# Page_H_B2B_A.net
KiCad netlist of a schematic drawn in Altium Designer
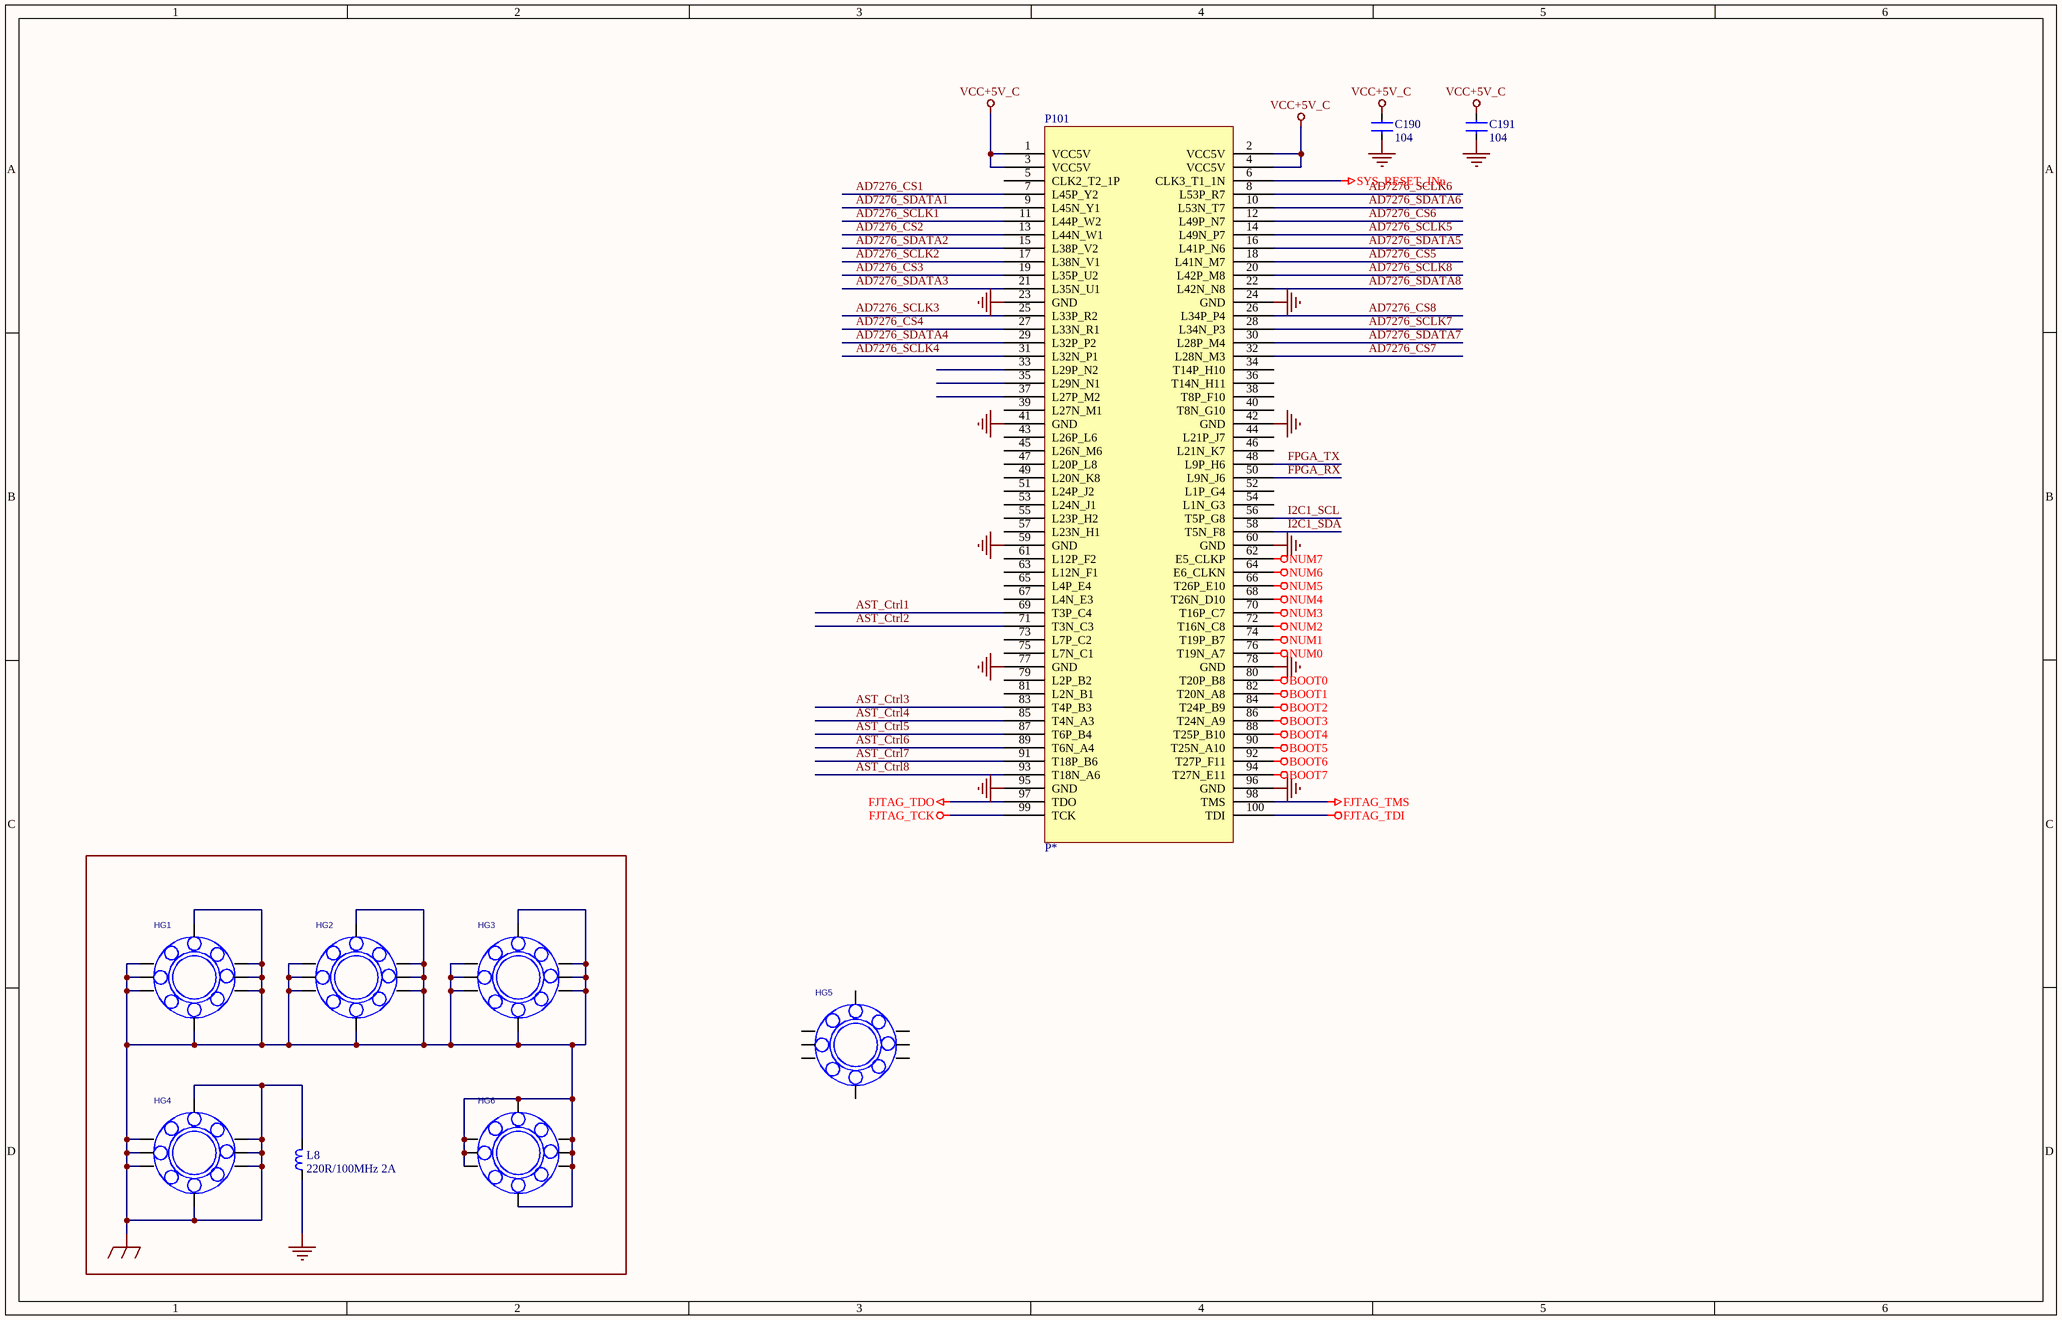
[diagram p0: Page H_B2B_A.SchDoc]

(export (version "E")
  (design (tool "Eeschema 10.0.6"))
  (components
    (comp (ref "C190")
      (value "104")
      (footprint "0603C")
      (description "C-X5R/X7R")
      (libsource (lib "贴片电阻电容") (part "C-X5R/X7R"))
    )
    (comp (ref "C191")
      (value "104")
      (footprint "0603C")
      (description "C-X5R/X7R")
      (libsource (lib "贴片电阻电容") (part "C-X5R/X7R"))
    )
    (comp (ref "HG1")
      (value "MOUNTING_HOLE_NL")
      (footprint "th126_196c_13c")
      (description "Sym, PCB mounting holes, th126_196c_13c")
      (libsource (lib "*") (part "MOUNTING_HOLE"))
    )
    (comp (ref "HG2")
      (value "MOUNTING_HOLE_NL")
      (footprint "th126_196c_13c")
      (description "Sym, PCB mounting holes, th126_196c_13c")
      (libsource (lib "*") (part "MOUNTING_HOLE"))
    )
    (comp (ref "HG3")
      (value "MOUNTING_HOLE_NL")
      (footprint "th126_196c_13c")
      (description "Sym, PCB mounting holes, th126_196c_13c")
      (libsource (lib "*") (part "MOUNTING_HOLE"))
    )
    (comp (ref "HG4")
      (value "MOUNTING_HOLE_NL")
      (footprint "th126_196c_13c")
      (description "Sym, PCB mounting holes, th126_196c_13c")
      (libsource (lib "*") (part "MOUNTING_HOLE"))
    )
    (comp (ref "HG5")
      (value "MOUNTING_HOLE_NL")
      (footprint "th126_196c_13c")
      (description "Sym, PCB mounting holes, th126_196c_13c")
      (libsource (lib "*") (part "MOUNTING_HOLE"))
    )
    (comp (ref "HG6")
      (value "MOUNTING_HOLE_NL")
      (footprint "th126_196c_13c")
      (description "Sym, PCB mounting holes, th126_196c_13c")
      (libsource (lib "*") (part "MOUNTING_HOLE"))
    )
    (comp (ref "L8")
      (value "220R/100MHz 2A")
      (footprint "0603R")
      (libsource (lib "电感、变压器件") (part "Inductor"))
    )
    (comp (ref "P101") (value "P*") (footprint "IDC100-05MM-SMD") (libsource (lib "3M") (part "IDC100")))
  )
  (nets
    (net (code "1") (name "/AD7276_CS1") (class "Default")
      (node (ref "P101") (pin "7") (pinfunction "L45P_Y2_7") (pintype "passive"))
    )
    (net (code "2") (name "/AD7276_CS2") (class "Default")
      (node (ref "P101") (pin "13") (pinfunction "L44N_W1_13") (pintype "passive"))
    )
    (net (code "3") (name "/AD7276_CS3") (class "Default")
      (node (ref "P101") (pin "19") (pinfunction "L35P_U2_19") (pintype "passive"))
    )
    (net (code "4") (name "/AD7276_CS4") (class "Default")
      (node (ref "P101") (pin "27") (pinfunction "L33N_R1_27") (pintype "passive"))
    )
    (net (code "5") (name "/AD7276_CS5") (class "Default")
      (node (ref "P101") (pin "18") (pinfunction "L41N_M7_18") (pintype "passive"))
    )
    (net (code "6") (name "/AD7276_CS6") (class "Default")
      (node (ref "P101") (pin "12") (pinfunction "L49P_N7_12") (pintype "passive"))
    )
    (net (code "7") (name "/AD7276_CS7") (class "Default")
      (node (ref "P101") (pin "32") (pinfunction "L28N_M3_32") (pintype "passive"))
    )
    (net (code "8") (name "/AD7276_CS8") (class "Default")
      (node (ref "P101") (pin "26") (pinfunction "L34P_P4_26") (pintype "passive"))
    )
    (net (code "9") (name "/AD7276_SCLK1") (class "Default")
      (node (ref "P101") (pin "11") (pinfunction "L44P_W2_11") (pintype "passive"))
    )
    (net (code "10") (name "/AD7276_SCLK2") (class "Default")
      (node (ref "P101") (pin "17") (pinfunction "L38N_V1_17") (pintype "passive"))
    )
    (net (code "11") (name "/AD7276_SCLK3") (class "Default")
      (node (ref "P101") (pin "25") (pinfunction "L33P_R2_25") (pintype "passive"))
    )
    (net (code "12") (name "/AD7276_SCLK4") (class "Default")
      (node (ref "P101") (pin "31") (pinfunction "L32N_P1_31") (pintype "passive"))
    )
    (net (code "13") (name "/AD7276_SCLK5") (class "Default")
      (node (ref "P101") (pin "14") (pinfunction "L49N_P7_14") (pintype "passive"))
    )
    (net (code "14") (name "/AD7276_SCLK6") (class "Default")
      (node (ref "P101") (pin "8") (pinfunction "L53P_R7_8") (pintype "passive"))
    )
    (net (code "15") (name "/AD7276_SCLK7") (class "Default")
      (node (ref "P101") (pin "28") (pinfunction "L34N_P3_28") (pintype "passive"))
    )
    (net (code "16") (name "/AD7276_SCLK8") (class "Default")
      (node (ref "P101") (pin "20") (pinfunction "L42P_M8_20") (pintype "passive"))
    )
    (net (code "17") (name "/AD7276_SDATA1") (class "Default")
      (node (ref "P101") (pin "9") (pinfunction "L45N_Y1_9") (pintype "passive"))
    )
    (net (code "18") (name "/AD7276_SDATA2") (class "Default")
      (node (ref "P101") (pin "15") (pinfunction "L38P_V2_15") (pintype "passive"))
    )
    (net (code "19") (name "/AD7276_SDATA3") (class "Default")
      (node (ref "P101") (pin "21") (pinfunction "L35N_U1_21") (pintype "passive"))
    )
    (net (code "20") (name "/AD7276_SDATA4") (class "Default")
      (node (ref "P101") (pin "29") (pinfunction "L32P_P2_29") (pintype "passive"))
    )
    (net (code "21") (name "/AD7276_SDATA5") (class "Default")
      (node (ref "P101") (pin "16") (pinfunction "L41P_N6_16") (pintype "passive"))
    )
    (net (code "22") (name "/AD7276_SDATA6") (class "Default")
      (node (ref "P101") (pin "10") (pinfunction "L53N_T7_10") (pintype "passive"))
    )
    (net (code "23") (name "/AD7276_SDATA7") (class "Default")
      (node (ref "P101") (pin "30") (pinfunction "L28P_M4_30") (pintype "passive"))
    )
    (net (code "24") (name "/AD7276_SDATA8") (class "Default")
      (node (ref "P101") (pin "22") (pinfunction "L42N_N8_22") (pintype "passive"))
    )
    (net (code "25") (name "/AST_Ctrl1") (class "Default")
      (node (ref "P101") (pin "69") (pinfunction "T3P_C4_69") (pintype "passive"))
    )
    (net (code "26") (name "/AST_Ctrl2") (class "Default")
      (node (ref "P101") (pin "71") (pinfunction "T3N_C3_71") (pintype "passive"))
    )
    (net (code "27") (name "/AST_Ctrl3") (class "Default")
      (node (ref "P101") (pin "83") (pinfunction "T4P_B3_83") (pintype "passive"))
    )
    (net (code "28") (name "/AST_Ctrl4") (class "Default")
      (node (ref "P101") (pin "85") (pinfunction "T4N_A3_85") (pintype "passive"))
    )
    (net (code "29") (name "/AST_Ctrl5") (class "Default")
      (node (ref "P101") (pin "87") (pinfunction "T6P_B4_87") (pintype "passive"))
    )
    (net (code "30") (name "/AST_Ctrl6") (class "Default")
      (node (ref "P101") (pin "89") (pinfunction "T6N_A4_89") (pintype "passive"))
    )
    (net (code "31") (name "/AST_Ctrl7") (class "Default")
      (node (ref "P101") (pin "91") (pinfunction "T18P_B6_91") (pintype "passive"))
    )
    (net (code "32") (name "/AST_Ctrl8") (class "Default")
      (node (ref "P101") (pin "93") (pinfunction "T18N_A6_93") (pintype "passive"))
    )
    (net (code "33") (name "/FPGA_RX") (class "Default")
      (node (ref "P101") (pin "50") (pinfunction "L9N_J6_50") (pintype "passive"))
    )
    (net (code "34") (name "/FPGA_TX") (class "Default")
      (node (ref "P101") (pin "48") (pinfunction "L9P_H6_48") (pintype "passive"))
    )
    (net (code "35") (name "/I2C1_SCL") (class "Default")
      (node (ref "P101") (pin "56") (pinfunction "T5P_G8_56") (pintype "passive"))
    )
    (net (code "36") (name "/I2C1_SDA") (class "Default")
      (node (ref "P101") (pin "58") (pinfunction "T5N_F8_58") (pintype "passive"))
    )
    (net (code "37") (name "BOOT0") (class "Default")
      (node (ref "P101") (pin "80") (pinfunction "T20P_B8_80") (pintype "passive"))
    )
    (net (code "38") (name "BOOT1") (class "Default")
      (node (ref "P101") (pin "82") (pinfunction "T20N_A8_82") (pintype "passive"))
    )
    (net (code "39") (name "BOOT2") (class "Default")
      (node (ref "P101") (pin "84") (pinfunction "T24P_B9_84") (pintype "passive"))
    )
    (net (code "40") (name "BOOT3") (class "Default")
      (node (ref "P101") (pin "86") (pinfunction "T24N_A9_86") (pintype "passive"))
    )
    (net (code "41") (name "BOOT4") (class "Default")
      (node (ref "P101") (pin "88") (pinfunction "T25P_B10_88") (pintype "passive"))
    )
    (net (code "42") (name "BOOT5") (class "Default")
      (node (ref "P101") (pin "90") (pinfunction "T25N_A10_90") (pintype "passive"))
    )
    (net (code "43") (name "BOOT6") (class "Default")
      (node (ref "P101") (pin "92") (pinfunction "T27P_F11_92") (pintype "passive"))
    )
    (net (code "44") (name "BOOT7") (class "Default")
      (node (ref "P101") (pin "94") (pinfunction "T27N_E11_94") (pintype "passive"))
    )
    (net (code "45") (name "FJTAG_TCK") (class "Default")
      (node (ref "P101") (pin "99") (pinfunction "TCK_99") (pintype "passive"))
    )
    (net (code "46") (name "FJTAG_TDI") (class "Default")
      (node (ref "P101") (pin "100") (pinfunction "TDI_100") (pintype "passive"))
    )
    (net (code "47") (name "FJTAG_TDO") (class "Default")
      (node (ref "P101") (pin "97") (pinfunction "TDO_97") (pintype "passive"))
    )
    (net (code "48") (name "FJTAG_TMS") (class "Default")
      (node (ref "P101") (pin "98") (pinfunction "TMS_98") (pintype "passive"))
    )
    (net (code "49") (name "GND") (class "Default")
      (node (ref "C190") (pin "1") (pinfunction "1_1") (pintype "passive"))
      (node (ref "C191") (pin "1") (pinfunction "1_1") (pintype "passive"))
      (node (ref "L8") (pin "1") (pinfunction "1_1") (pintype "passive"))
      (node (ref "P101") (pin "23") (pinfunction "GND_23") (pintype "passive"))
      (node (ref "P101") (pin "24") (pinfunction "GND_24") (pintype "passive"))
      (node (ref "P101") (pin "41") (pinfunction "GND_41") (pintype "passive"))
      (node (ref "P101") (pin "42") (pinfunction "GND_42") (pintype "passive"))
      (node (ref "P101") (pin "59") (pinfunction "GND_59") (pintype "passive"))
      (node (ref "P101") (pin "60") (pinfunction "GND_60") (pintype "passive"))
      (node (ref "P101") (pin "77") (pinfunction "GND_77") (pintype "passive"))
      (node (ref "P101") (pin "78") (pinfunction "GND_78") (pintype "passive"))
      (node (ref "P101") (pin "95") (pinfunction "GND_95") (pintype "passive"))
      (node (ref "P101") (pin "96") (pinfunction "GND_96") (pintype "passive"))
    )
    (net (code "50") (name "GND_EARTH") (class "Default")
      (node (ref "HG1") (pin "1") (pinfunction "G1_1") (pintype "passive"))
      (node (ref "HG1") (pin "2") (pinfunction "G2_2") (pintype "passive"))
      (node (ref "HG1") (pin "3") (pinfunction "G3_3") (pintype "passive"))
      (node (ref "HG1") (pin "4") (pinfunction "G4_4") (pintype "passive"))
      (node (ref "HG1") (pin "5") (pinfunction "G5_5") (pintype "passive"))
      (node (ref "HG1") (pin "6") (pinfunction "G6_6") (pintype "passive"))
      (node (ref "HG1") (pin "7") (pinfunction "G7_7") (pintype "passive"))
      (node (ref "HG1") (pin "8") (pinfunction "G8_8") (pintype "passive"))
      (node (ref "HG2") (pin "1") (pinfunction "G1_1") (pintype "passive"))
      (node (ref "HG2") (pin "2") (pinfunction "G2_2") (pintype "passive"))
      (node (ref "HG2") (pin "3") (pinfunction "G3_3") (pintype "passive"))
      (node (ref "HG2") (pin "4") (pinfunction "G4_4") (pintype "passive"))
      (node (ref "HG2") (pin "5") (pinfunction "G5_5") (pintype "passive"))
      (node (ref "HG2") (pin "6") (pinfunction "G6_6") (pintype "passive"))
      (node (ref "HG2") (pin "7") (pinfunction "G7_7") (pintype "passive"))
      (node (ref "HG2") (pin "8") (pinfunction "G8_8") (pintype "passive"))
      (node (ref "HG3") (pin "1") (pinfunction "G1_1") (pintype "passive"))
      (node (ref "HG3") (pin "2") (pinfunction "G2_2") (pintype "passive"))
      (node (ref "HG3") (pin "3") (pinfunction "G3_3") (pintype "passive"))
      (node (ref "HG3") (pin "4") (pinfunction "G4_4") (pintype "passive"))
      (node (ref "HG3") (pin "5") (pinfunction "G5_5") (pintype "passive"))
      (node (ref "HG3") (pin "6") (pinfunction "G6_6") (pintype "passive"))
      (node (ref "HG3") (pin "7") (pinfunction "G7_7") (pintype "passive"))
      (node (ref "HG3") (pin "8") (pinfunction "G8_8") (pintype "passive"))
      (node (ref "HG4") (pin "1") (pinfunction "G1_1") (pintype "passive"))
      (node (ref "HG4") (pin "2") (pinfunction "G2_2") (pintype "passive"))
      (node (ref "HG4") (pin "3") (pinfunction "G3_3") (pintype "passive"))
      (node (ref "HG4") (pin "4") (pinfunction "G4_4") (pintype "passive"))
      (node (ref "HG4") (pin "5") (pinfunction "G5_5") (pintype "passive"))
      (node (ref "HG4") (pin "6") (pinfunction "G6_6") (pintype "passive"))
      (node (ref "HG4") (pin "7") (pinfunction "G7_7") (pintype "passive"))
      (node (ref "HG4") (pin "8") (pinfunction "G8_8") (pintype "passive"))
      (node (ref "HG6") (pin "1") (pinfunction "G1_1") (pintype "passive"))
      (node (ref "HG6") (pin "2") (pinfunction "G2_2") (pintype "passive"))
      (node (ref "HG6") (pin "3") (pinfunction "G3_3") (pintype "passive"))
      (node (ref "HG6") (pin "4") (pinfunction "G4_4") (pintype "passive"))
      (node (ref "HG6") (pin "5") (pinfunction "G5_5") (pintype "passive"))
      (node (ref "HG6") (pin "6") (pinfunction "G6_6") (pintype "passive"))
      (node (ref "HG6") (pin "7") (pinfunction "G7_7") (pintype "passive"))
      (node (ref "HG6") (pin "8") (pinfunction "G8_8") (pintype "passive"))
      (node (ref "L8") (pin "2") (pinfunction "2_2") (pintype "passive"))
    )
    (net (code "51") (name "NUM0") (class "Default")
      (node (ref "P101") (pin "76") (pinfunction "T19N_A7_76") (pintype "passive"))
    )
    (net (code "52") (name "NUM1") (class "Default")
      (node (ref "P101") (pin "74") (pinfunction "T19P_B7_74") (pintype "passive"))
    )
    (net (code "53") (name "NUM2") (class "Default")
      (node (ref "P101") (pin "72") (pinfunction "T16N_C8_72") (pintype "passive"))
    )
    (net (code "54") (name "NUM3") (class "Default")
      (node (ref "P101") (pin "70") (pinfunction "T16P_C7_70") (pintype "passive"))
    )
    (net (code "55") (name "NUM4") (class "Default")
      (node (ref "P101") (pin "68") (pinfunction "T26N_D10_68") (pintype "passive"))
    )
    (net (code "56") (name "NUM5") (class "Default")
      (node (ref "P101") (pin "66") (pinfunction "T26P_E10_66") (pintype "passive"))
    )
    (net (code "57") (name "NUM6") (class "Default")
      (node (ref "P101") (pin "64") (pinfunction "E6_CLKN_64") (pintype "passive"))
    )
    (net (code "58") (name "NUM7") (class "Default")
      (node (ref "P101") (pin "62") (pinfunction "E5_CLKP_62") (pintype "passive"))
    )
    (net (code "59") (name "SYS_RESET_INn") (class "Default")
      (node (ref "P101") (pin "6") (pinfunction "CLK3_T1_1N_6") (pintype "passive"))
    )
    (net (code "60") (name "VCC+5V_C") (class "Default")
      (node (ref "C190") (pin "2") (pinfunction "2_2") (pintype "passive"))
      (node (ref "C191") (pin "2") (pinfunction "2_2") (pintype "passive"))
      (node (ref "P101") (pin "1") (pinfunction "VCC5V_1") (pintype "passive"))
      (node (ref "P101") (pin "2") (pinfunction "VCC5V_2") (pintype "passive"))
      (node (ref "P101") (pin "3") (pinfunction "VCC5V_3") (pintype "passive"))
      (node (ref "P101") (pin "4") (pinfunction "VCC5V_4") (pintype "passive"))
    )
    (net (code "61") (name "unconnected-(HG5-G1-Pad1)") (class "Default")
      (node (ref "HG5") (pin "1") (pinfunction "G1_1") (pintype "passive"))
    )
    (net (code "62") (name "unconnected-(HG5-G2-Pad2)") (class "Default")
      (node (ref "HG5") (pin "2") (pinfunction "G2_2") (pintype "passive"))
    )
    (net (code "63") (name "unconnected-(HG5-G3-Pad3)") (class "Default")
      (node (ref "HG5") (pin "3") (pinfunction "G3_3") (pintype "passive"))
    )
    (net (code "64") (name "unconnected-(HG5-G4-Pad4)") (class "Default")
      (node (ref "HG5") (pin "4") (pinfunction "G4_4") (pintype "passive"))
    )
    (net (code "65") (name "unconnected-(HG5-G5-Pad5)") (class "Default")
      (node (ref "HG5") (pin "5") (pinfunction "G5_5") (pintype "passive"))
    )
    (net (code "66") (name "unconnected-(HG5-G6-Pad6)") (class "Default")
      (node (ref "HG5") (pin "6") (pinfunction "G6_6") (pintype "passive"))
    )
    (net (code "67") (name "unconnected-(HG5-G7-Pad7)") (class "Default")
      (node (ref "HG5") (pin "7") (pinfunction "G7_7") (pintype "passive"))
    )
    (net (code "68") (name "unconnected-(HG5-G8-Pad8)") (class "Default")
      (node (ref "HG5") (pin "8") (pinfunction "G8_8") (pintype "passive"))
    )
    (net (code "69") (name "unconnected-(P101-CLK2_T2_1P-Pad5)") (class "Default")
      (node (ref "P101") (pin "5") (pinfunction "CLK2_T2_1P_5") (pintype "passive"))
    )
    (net (code "70") (name "unconnected-(P101-L1N_G3-Pad54)") (class "Default")
      (node (ref "P101") (pin "54") (pinfunction "L1N_G3_54") (pintype "passive"))
    )
    (net (code "71") (name "unconnected-(P101-L1P_G4-Pad52)") (class "Default")
      (node (ref "P101") (pin "52") (pinfunction "L1P_G4_52") (pintype "passive"))
    )
    (net (code "72") (name "unconnected-(P101-L2N_B1-Pad81)") (class "Default")
      (node (ref "P101") (pin "81") (pinfunction "L2N_B1_81") (pintype "passive"))
    )
    (net (code "73") (name "unconnected-(P101-L2P_B2-Pad79)") (class "Default")
      (node (ref "P101") (pin "79") (pinfunction "L2P_B2_79") (pintype "passive"))
    )
    (net (code "74") (name "unconnected-(P101-L4N_E3-Pad67)") (class "Default")
      (node (ref "P101") (pin "67") (pinfunction "L4N_E3_67") (pintype "passive"))
    )
    (net (code "75") (name "unconnected-(P101-L4P_E4-Pad65)") (class "Default")
      (node (ref "P101") (pin "65") (pinfunction "L4P_E4_65") (pintype "passive"))
    )
    (net (code "76") (name "unconnected-(P101-L7N_C1-Pad75)") (class "Default")
      (node (ref "P101") (pin "75") (pinfunction "L7N_C1_75") (pintype "passive"))
    )
    (net (code "77") (name "unconnected-(P101-L7P_C2-Pad73)") (class "Default")
      (node (ref "P101") (pin "73") (pinfunction "L7P_C2_73") (pintype "passive"))
    )
    (net (code "78") (name "unconnected-(P101-L12N_F1-Pad63)") (class "Default")
      (node (ref "P101") (pin "63") (pinfunction "L12N_F1_63") (pintype "passive"))
    )
    (net (code "79") (name "unconnected-(P101-L12P_F2-Pad61)") (class "Default")
      (node (ref "P101") (pin "61") (pinfunction "L12P_F2_61") (pintype "passive"))
    )
    (net (code "80") (name "unconnected-(P101-L20N_K8-Pad49)") (class "Default")
      (node (ref "P101") (pin "49") (pinfunction "L20N_K8_49") (pintype "passive"))
    )
    (net (code "81") (name "unconnected-(P101-L20P_L8-Pad47)") (class "Default")
      (node (ref "P101") (pin "47") (pinfunction "L20P_L8_47") (pintype "passive"))
    )
    (net (code "82") (name "unconnected-(P101-L21N_K7-Pad46)") (class "Default")
      (node (ref "P101") (pin "46") (pinfunction "L21N_K7_46") (pintype "passive"))
    )
    (net (code "83") (name "unconnected-(P101-L21P_J7-Pad44)") (class "Default")
      (node (ref "P101") (pin "44") (pinfunction "L21P_J7_44") (pintype "passive"))
    )
    (net (code "84") (name "unconnected-(P101-L23N_H1-Pad57)") (class "Default")
      (node (ref "P101") (pin "57") (pinfunction "L23N_H1_57") (pintype "passive"))
    )
    (net (code "85") (name "unconnected-(P101-L23P_H2-Pad55)") (class "Default")
      (node (ref "P101") (pin "55") (pinfunction "L23P_H2_55") (pintype "passive"))
    )
    (net (code "86") (name "unconnected-(P101-L24N_J1-Pad53)") (class "Default")
      (node (ref "P101") (pin "53") (pinfunction "L24N_J1_53") (pintype "passive"))
    )
    (net (code "87") (name "unconnected-(P101-L24P_J2-Pad51)") (class "Default")
      (node (ref "P101") (pin "51") (pinfunction "L24P_J2_51") (pintype "passive"))
    )
    (net (code "88") (name "unconnected-(P101-L26N_M6-Pad45)") (class "Default")
      (node (ref "P101") (pin "45") (pinfunction "L26N_M6_45") (pintype "passive"))
    )
    (net (code "89") (name "unconnected-(P101-L26P_L6-Pad43)") (class "Default")
      (node (ref "P101") (pin "43") (pinfunction "L26P_L6_43") (pintype "passive"))
    )
    (net (code "90") (name "unconnected-(P101-L27N_M1-Pad39)") (class "Default")
      (node (ref "P101") (pin "39") (pinfunction "L27N_M1_39") (pintype "passive"))
    )
    (net (code "91") (name "unconnected-(P101-L27P_M2-Pad37)") (class "Default")
      (node (ref "P101") (pin "37") (pinfunction "L27P_M2_37") (pintype "passive"))
    )
    (net (code "92") (name "unconnected-(P101-L29N_N1-Pad35)") (class "Default")
      (node (ref "P101") (pin "35") (pinfunction "L29N_N1_35") (pintype "passive"))
    )
    (net (code "93") (name "unconnected-(P101-L29P_N2-Pad33)") (class "Default")
      (node (ref "P101") (pin "33") (pinfunction "L29P_N2_33") (pintype "passive"))
    )
    (net (code "94") (name "unconnected-(P101-T8N_G10-Pad40)") (class "Default")
      (node (ref "P101") (pin "40") (pinfunction "T8N_G10_40") (pintype "passive"))
    )
    (net (code "95") (name "unconnected-(P101-T8P_F10-Pad38)") (class "Default")
      (node (ref "P101") (pin "38") (pinfunction "T8P_F10_38") (pintype "passive"))
    )
    (net (code "96") (name "unconnected-(P101-T14N_H11-Pad36)") (class "Default")
      (node (ref "P101") (pin "36") (pinfunction "T14N_H11_36") (pintype "passive"))
    )
    (net (code "97") (name "unconnected-(P101-T14P_H10-Pad34)") (class "Default")
      (node (ref "P101") (pin "34") (pinfunction "T14P_H10_34") (pintype "passive"))
    )
  )
)
